# principal.net
KiCad netlist of a schematic drawn in Altium Designer
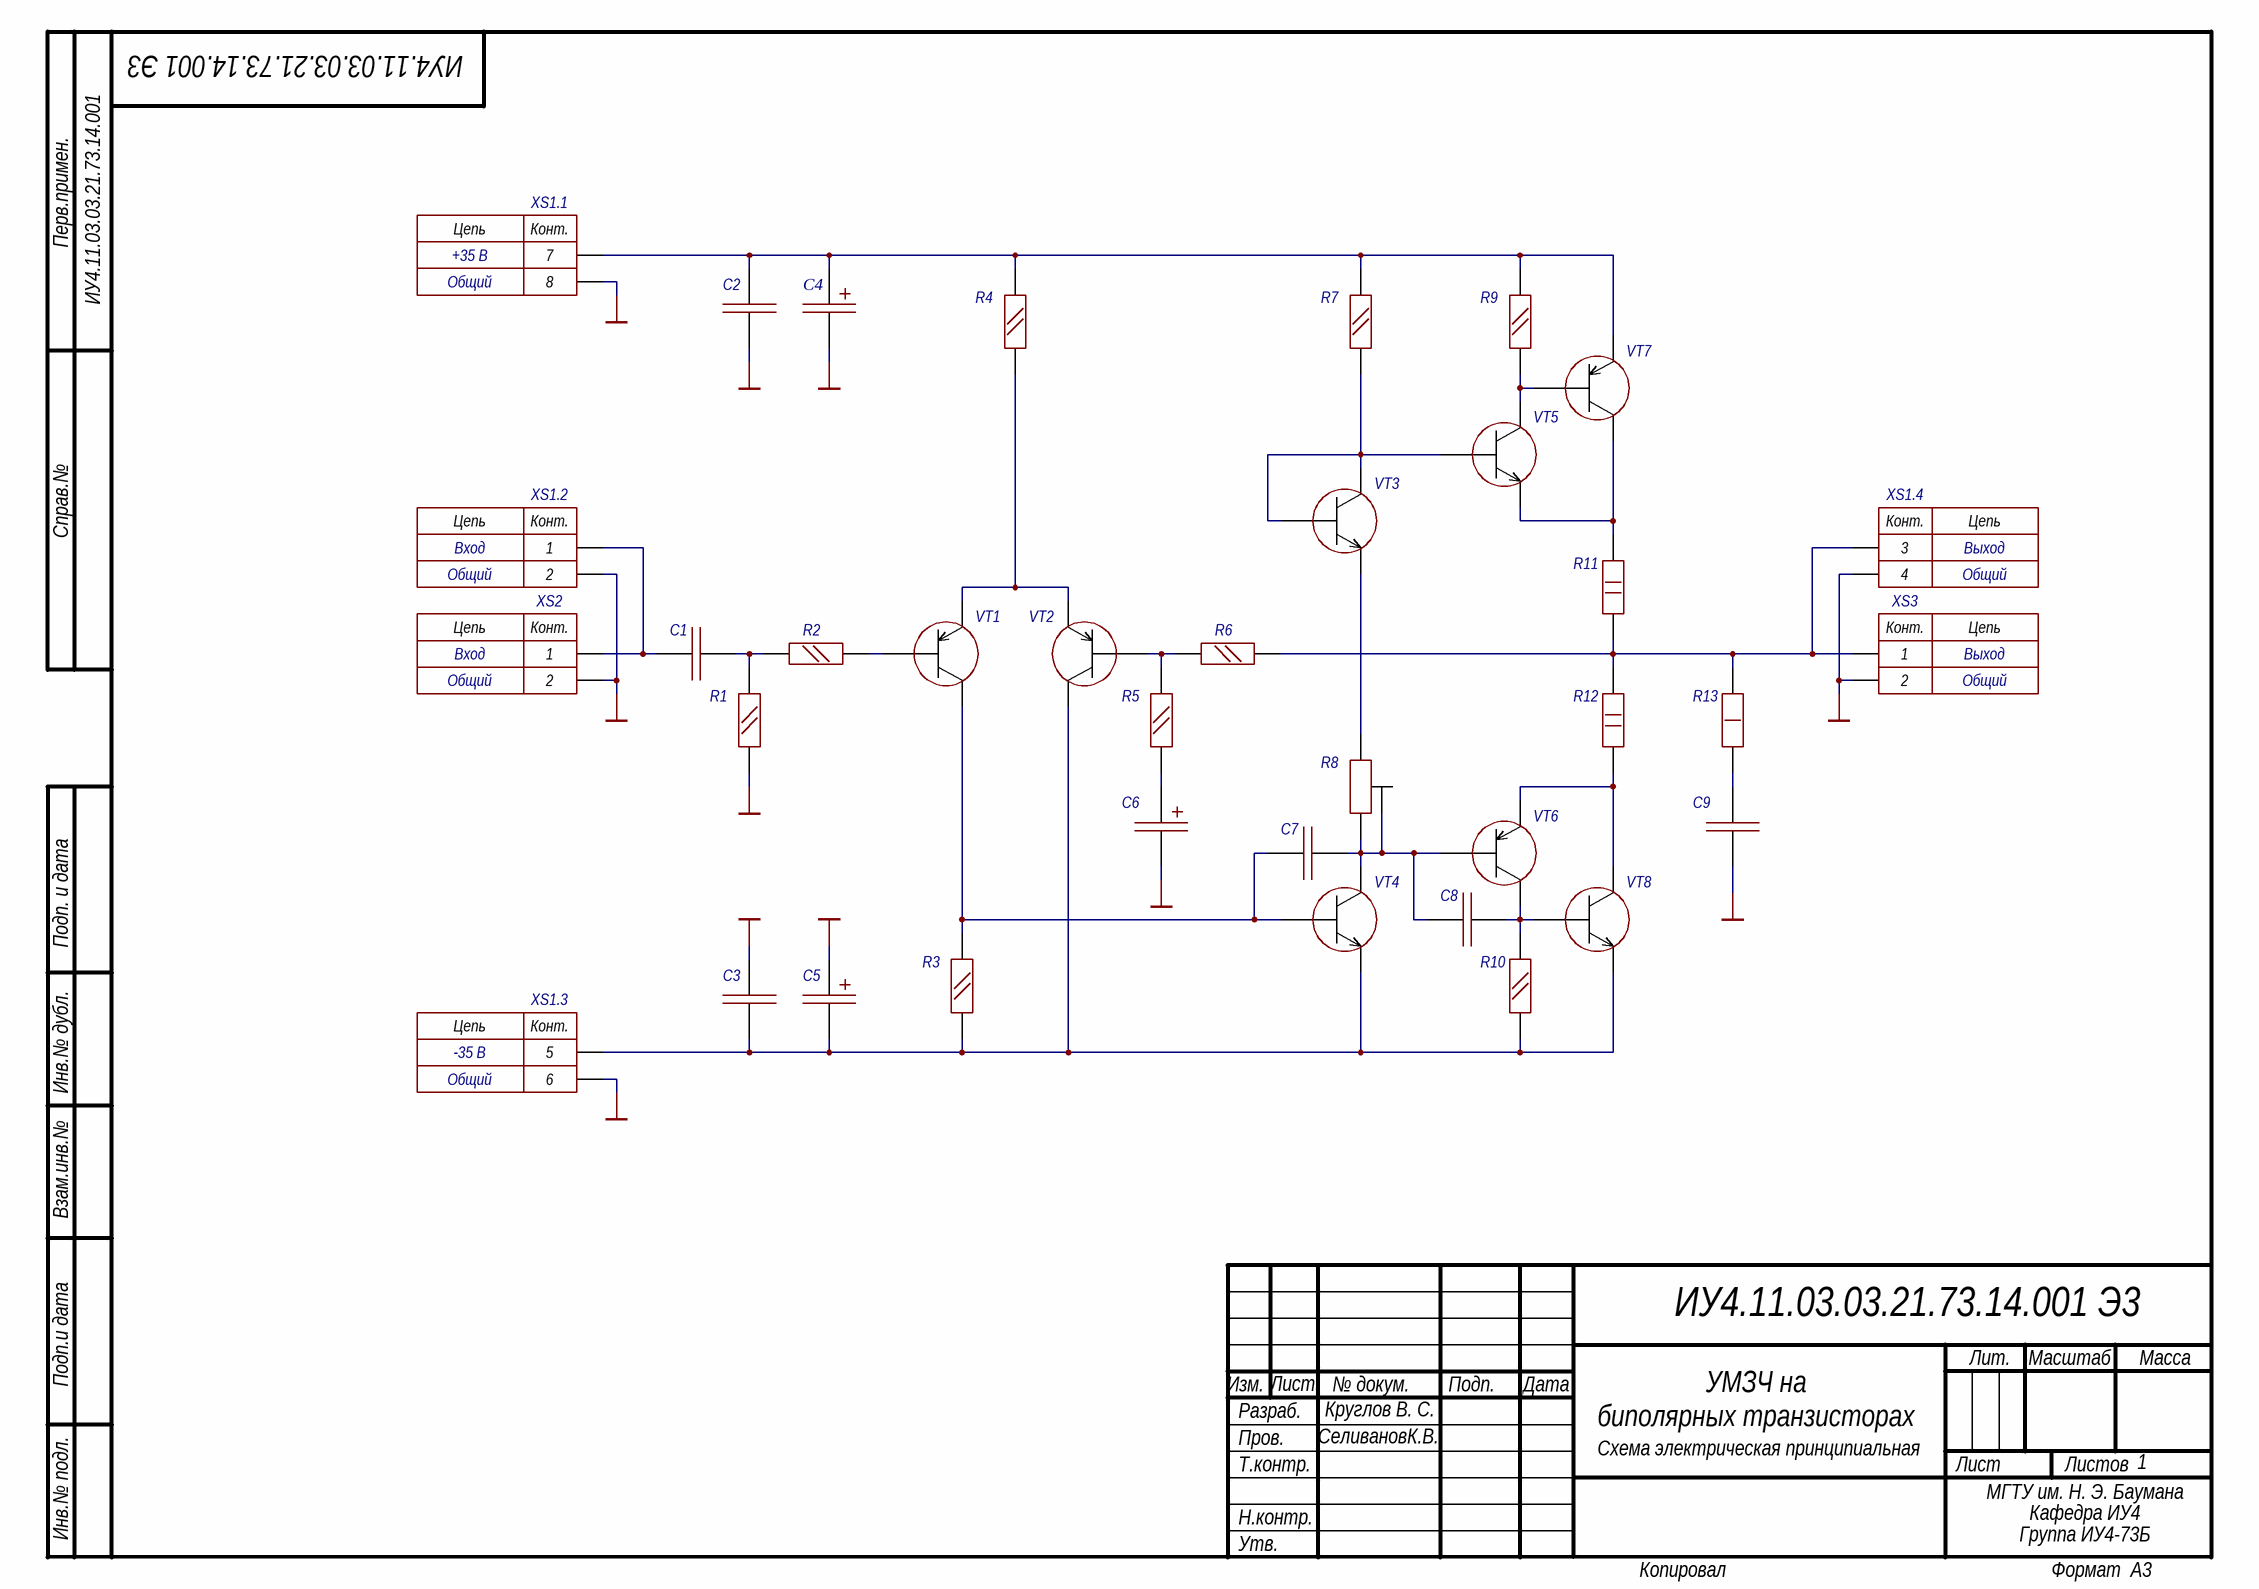
[diagram p0: principal.SchDoc]

(export (version "E")
  (design (tool "Eeschema 10.0.6"))
  (components
    (comp (ref "C1")
      (value "Capacitor")
      (footprint "C_PLY_10X5")
      (libsource (lib "Components - 07.07.24 - 20.56") (part "Capacitor"))
    )
    (comp (ref "C2")
      (value "Capacitor")
      (footprint "C_PLY_10X5")
      (libsource (lib "Components - 07.07.24 - 20.56") (part "Capacitor"))
    )
    (comp (ref "C3")
      (value "Capacitor")
      (footprint "C_PLY_10X5")
      (libsource (lib "Components - 07.07.24 - 20.56") (part "Capacitor"))
    )
    (comp (ref "C4")
      (value "Capactor polar")
      (footprint "C_EL_12X25")
      (libsource (lib "Components - 07.07.24 - 20.56") (part "Capactor polar"))
    )
    (comp (ref "C5")
      (value "Capactor polar")
      (footprint "C_EL_12X25")
      (libsource (lib "Components - 07.07.24 - 20.56") (part "Capactor polar"))
    )
    (comp (ref "C6")
      (value "Capactor polar")
      (footprint "C_EL_4X7")
      (libsource (lib "Components - 07.07.24 - 20.56") (part "Capactor polar"))
    )
    (comp (ref "C7")
      (value "Capacitor")
      (footprint "C_PLY_7X5")
      (libsource (lib "Components - 07.07.24 - 20.56") (part "Capacitor"))
    )
    (comp (ref "C8")
      (value "Capacitor")
      (footprint "C_PLY_7X5")
      (libsource (lib "Components - 07.07.24 - 20.56") (part "Capacitor"))
    )
    (comp (ref "C9")
      (value "Capacitor")
      (footprint "C_PLY_10X5")
      (libsource (lib "Components - 07.07.24 - 20.56") (part "Capacitor"))
    )
    (comp (ref "R1")
      (value "Res")
      (footprint "R0125W_AX025")
      (libsource (lib "Integrated_Library_PAAF") (part "Res"))
    )
    (comp (ref "R2") (value "Res") (footprint "R0125W_AX025") (libsource (lib "") (part "Res_1")))
    (comp (ref "R3")
      (value "Res")
      (footprint "R0125W_AX025")
      (libsource (lib "Integrated_Library_PAAF") (part "Res"))
    )
    (comp (ref "R4")
      (value "Res")
      (footprint "R0125W_AX025")
      (libsource (lib "Integrated_Library_PAAF") (part "Res"))
    )
    (comp (ref "R5")
      (value "Res")
      (footprint "R0125W_AX025")
      (libsource (lib "Integrated_Library_PAAF") (part "Res"))
    )
    (comp (ref "R6") (value "Res") (footprint "R0125W_AX025") (libsource (lib "") (part "Res_1")))
    (comp (ref "R7")
      (value "Res")
      (footprint "R0125W_AX025")
      (libsource (lib "Integrated_Library_PAAF") (part "Res"))
    )
    (comp (ref "R8")
      (value "POT")
      (footprint "POT_3296W")
      (libsource (lib "Integrated_Library_PAAF") (part "POT"))
    )
    (comp (ref "R9")
      (value "Res")
      (footprint "R0125W_AX025")
      (libsource (lib "Integrated_Library_PAAF") (part "Res"))
    )
    (comp (ref "R10")
      (value "Res")
      (footprint "R0125W_AX025")
      (libsource (lib "Integrated_Library_PAAF") (part "Res"))
    )
    (comp (ref "R11")
      (value "Res")
      (footprint "R2W_AX08")
      (libsource (lib "Integrated_Library_PAAF") (part "Res"))
    )
    (comp (ref "R12")
      (value "Res")
      (footprint "R2W_AX08")
      (libsource (lib "Integrated_Library_PAAF") (part "Res"))
    )
    (comp (ref "R13")
      (value "Res")
      (footprint "R1W_AX06")
      (libsource (lib "Integrated_Library_PAAF") (part "Res"))
    )
    (comp (ref "VT1")
      (value "Transistor_PNP")
      (footprint "TO92_3FB")
      (libsource (lib "Sch") (part "Transistor_PNP"))
    )
    (comp (ref "VT2")
      (value "Transistor_PNP")
      (footprint "TO92_3FB")
      (libsource (lib "Sch") (part "Transistor_PNP"))
    )
    (comp (ref "VT3")
      (value "BD139G")
      (footprint "TO126_3")
      (libsource (lib "Components - 07.07.24 - 21.07") (part "Transistor_NPN"))
    )
    (comp (ref "VT4")
      (value "BD139G")
      (footprint "TO220_3")
      (libsource (lib "Components - 07.07.24 - 21.07") (part "Transistor_NPN"))
    )
    (comp (ref "VT5")
      (value "BD139G")
      (footprint "TO126_3")
      (libsource (lib "Components - 07.07.24 - 21.07") (part "Transistor_NPN"))
    )
    (comp (ref "VT6")
      (value "Transistor_PNP")
      (footprint "TO126_3")
      (libsource (lib "Sch") (part "Transistor_PNP"))
    )
    (comp (ref "VT7")
      (value "Transistor_PNP")
      (footprint "TO247_3")
      (libsource (lib "Sch") (part "Transistor_PNP"))
    )
    (comp (ref "VT8")
      (value "BD139G")
      (footprint "TO247_3")
      (libsource (lib "Components - 07.07.24 - 21.07") (part "Transistor_NPN"))
    )
    (comp (ref "XP1")
      (value "CONN")
      (footprint "MOLEX_430450821")
      (libsource (lib "Components - 07.07.24 - 20.56") (part "CONN"))
    )
    (comp (ref "XS1")
      (value "Audio")
      (footprint "FP-NMJ4HFD2-MFG")
      (libsource (lib "Integrated_Library_PAAF") (part "Audio"))
    )
    (comp (ref "XS2")
      (value "Audio")
      (footprint "FP-NMJ4HFD2-MFG")
      (libsource (lib "Integrated_Library_PAAF") (part "Audio"))
    )
  )
  (nets
    (net (code "1") (name "GND") (class "Default")
      (node (ref "C2") (pin "2") (pinfunction "2_2") (pintype "passive"))
      (node (ref "C3") (pin "2") (pinfunction "2_2") (pintype "passive"))
      (node (ref "C4") (pin "1") (pinfunction "1_1") (pintype "passive"))
      (node (ref "C5") (pin "2") (pinfunction "2_2") (pintype "passive"))
      (node (ref "C6") (pin "1") (pinfunction "1_1") (pintype "passive"))
      (node (ref "C9") (pin "2") (pinfunction "2_2") (pintype "passive"))
      (node (ref "R1") (pin "1") (pinfunction "1_1") (pintype "passive"))
      (node (ref "XP1") (pin "2") (pintype "passive"))
      (node (ref "XP1") (pin "4") (pintype "passive"))
      (node (ref "XP1") (pin "6") (pintype "passive"))
      (node (ref "XP1") (pin "8") (pintype "passive"))
      (node (ref "XS1") (pin "2") (pintype "passive"))
      (node (ref "XS2") (pin "2") (pintype "passive"))
    )
    (net (code "2") (name "Net-(C1-Pad1)") (class "Default")
      (node (ref "C1") (pin "1") (pinfunction "1_1") (pintype "passive"))
      (node (ref "XP1") (pin "1") (pintype "passive"))
      (node (ref "XS1") (pin "1") (pintype "passive"))
    )
    (net (code "3") (name "Net-(C1-Pad2)") (class "Default")
      (node (ref "C1") (pin "2") (pinfunction "2_2") (pintype "passive"))
      (node (ref "R1") (pin "2") (pinfunction "2_2") (pintype "passive"))
      (node (ref "R2") (pin "2") (pinfunction "2_2") (pintype "passive"))
    )
    (net (code "4") (name "Net-(C6-Pad2)") (class "Default")
      (node (ref "C6") (pin "2") (pinfunction "2_2") (pintype "passive"))
      (node (ref "R5") (pin "1") (pinfunction "1_1") (pintype "passive"))
    )
    (net (code "5") (name "Net-(C9-Pad1)") (class "Default")
      (node (ref "C9") (pin "1") (pinfunction "1_1") (pintype "passive"))
      (node (ref "R13") (pin "1") (pinfunction "1_1") (pintype "passive"))
    )
    (net (code "6") (name "Net-(R11-Pad1)") (class "Default")
      (node (ref "R11") (pin "1") (pinfunction "1_1") (pintype "passive"))
      (node (ref "R12") (pin "2") (pinfunction "2_2") (pintype "passive"))
      (node (ref "R13") (pin "2") (pinfunction "2_2") (pintype "passive"))
      (node (ref "R6") (pin "1") (pinfunction "1_1") (pintype "passive"))
      (node (ref "XP1") (pin "3") (pintype "passive"))
      (node (ref "XS2") (pin "1") (pintype "passive"))
    )
    (net (code "7") (name "Net-(VT1-B)") (class "Default")
      (node (ref "R2") (pin "1") (pinfunction "1_1") (pintype "passive"))
      (node (ref "VT1") (pin "3") (pinfunction "B_3") (pintype "passive"))
    )
    (net (code "8") (name "Net-(VT1-C)") (class "Default")
      (node (ref "C7") (pin "1") (pinfunction "1_1") (pintype "passive"))
      (node (ref "R3") (pin "2") (pinfunction "2_2") (pintype "passive"))
      (node (ref "VT1") (pin "2") (pinfunction "C_2") (pintype "passive"))
      (node (ref "VT4") (pin "3") (pinfunction "B_3") (pintype "passive"))
    )
    (net (code "9") (name "Net-(VT1-E)") (class "Default")
      (node (ref "R4") (pin "1") (pinfunction "1_1") (pintype "passive"))
      (node (ref "VT1") (pin "1") (pinfunction "E_1") (pintype "passive"))
      (node (ref "VT2") (pin "1") (pinfunction "E_1") (pintype "passive"))
    )
    (net (code "10") (name "Net-(VT2-B)") (class "Default")
      (node (ref "R5") (pin "2") (pinfunction "2_2") (pintype "passive"))
      (node (ref "R6") (pin "2") (pinfunction "2_2") (pintype "passive"))
      (node (ref "VT2") (pin "3") (pinfunction "B_3") (pintype "passive"))
    )
    (net (code "11") (name "Net-(VT2-C)") (class "Default")
      (node (ref "C3") (pin "1") (pinfunction "1_1") (pintype "passive"))
      (node (ref "C5") (pin "1") (pinfunction "1_1") (pintype "passive"))
      (node (ref "R10") (pin "1") (pinfunction "1_1") (pintype "passive"))
      (node (ref "R3") (pin "1") (pinfunction "1_1") (pintype "passive"))
      (node (ref "VT2") (pin "2") (pinfunction "C_2") (pintype "passive"))
      (node (ref "VT4") (pin "1") (pinfunction "E_1") (pintype "passive"))
      (node (ref "VT8") (pin "1") (pinfunction "E_1") (pintype "passive"))
      (node (ref "XP1") (pin "5") (pintype "passive"))
    )
    (net (code "12") (name "Net-(VT3-B)") (class "Default")
      (node (ref "R7") (pin "1") (pinfunction "1_1") (pintype "passive"))
      (node (ref "VT3") (pin "2") (pinfunction "C_2") (pintype "passive"))
      (node (ref "VT3") (pin "3") (pinfunction "B_3") (pintype "passive"))
      (node (ref "VT5") (pin "3") (pinfunction "B_3") (pintype "passive"))
    )
    (net (code "13") (name "Net-(VT3-E)") (class "Default")
      (node (ref "R8") (pin "1") (pinfunction "1_1") (pintype "passive"))
      (node (ref "VT3") (pin "1") (pinfunction "E_1") (pintype "passive"))
    )
    (net (code "14") (name "Net-(VT4-C)") (class "Default")
      (node (ref "C7") (pin "2") (pinfunction "2_2") (pintype "passive"))
      (node (ref "C8") (pin "1") (pinfunction "1_1") (pintype "passive"))
      (node (ref "R8") (pin "2") (pinfunction "2_2") (pintype "passive"))
      (node (ref "R8") (pin "3") (pinfunction "3_3") (pintype "passive"))
      (node (ref "VT4") (pin "2") (pinfunction "C_2") (pintype "passive"))
      (node (ref "VT6") (pin "3") (pinfunction "B_3") (pintype "passive"))
    )
    (net (code "15") (name "Net-(VT5-C)") (class "Default")
      (node (ref "R9") (pin "1") (pinfunction "1_1") (pintype "passive"))
      (node (ref "VT5") (pin "2") (pinfunction "C_2") (pintype "passive"))
      (node (ref "VT7") (pin "3") (pinfunction "B_3") (pintype "passive"))
    )
    (net (code "16") (name "Net-(VT5-E)") (class "Default")
      (node (ref "R11") (pin "2") (pinfunction "2_2") (pintype "passive"))
      (node (ref "VT5") (pin "1") (pinfunction "E_1") (pintype "passive"))
      (node (ref "VT7") (pin "2") (pinfunction "C_2") (pintype "passive"))
    )
    (net (code "17") (name "Net-(VT6-C)") (class "Default")
      (node (ref "C8") (pin "2") (pinfunction "2_2") (pintype "passive"))
      (node (ref "R10") (pin "2") (pinfunction "2_2") (pintype "passive"))
      (node (ref "VT6") (pin "2") (pinfunction "C_2") (pintype "passive"))
      (node (ref "VT8") (pin "3") (pinfunction "B_3") (pintype "passive"))
    )
    (net (code "18") (name "Net-(VT6-E)") (class "Default")
      (node (ref "R12") (pin "1") (pinfunction "1_1") (pintype "passive"))
      (node (ref "VT6") (pin "1") (pinfunction "E_1") (pintype "passive"))
      (node (ref "VT8") (pin "2") (pinfunction "C_2") (pintype "passive"))
    )
    (net (code "19") (name "Net-(VT7-E)") (class "Default")
      (node (ref "C2") (pin "1") (pinfunction "1_1") (pintype "passive"))
      (node (ref "C4") (pin "2") (pinfunction "2_2") (pintype "passive"))
      (node (ref "R4") (pin "2") (pinfunction "2_2") (pintype "passive"))
      (node (ref "R7") (pin "2") (pinfunction "2_2") (pintype "passive"))
      (node (ref "R9") (pin "2") (pinfunction "2_2") (pintype "passive"))
      (node (ref "VT7") (pin "1") (pinfunction "E_1") (pintype "passive"))
      (node (ref "XP1") (pin "7") (pintype "passive"))
    )
  )
)
